# STM32G070_prototype.net
KiCad netlist of a schematic drawn in Altium Designer
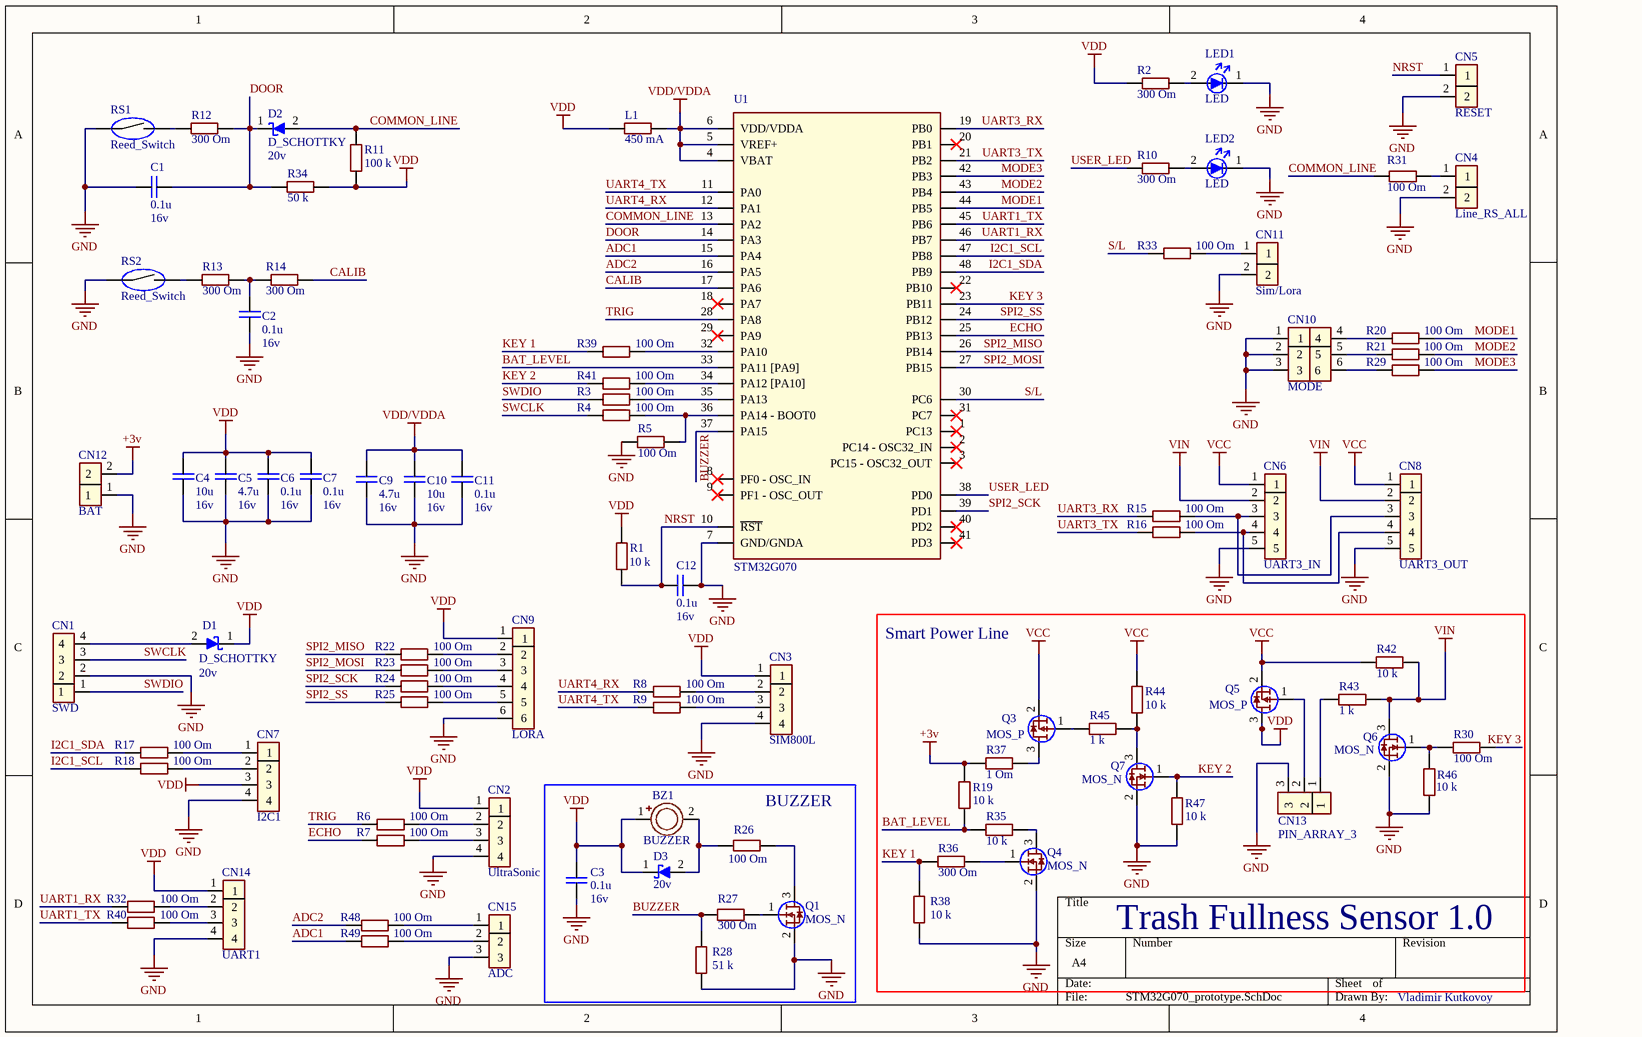
[diagram p0: STM32G070_prototype.SchDoc]

(export (version "E")
  (design (tool "Eeschema 10.0.6"))
  (components
    (comp (ref "BZ1") (value "BUZZER") (footprint "VK_Lib:BUZZER") (libsource (lib "Sound") (part "BUZZER")))
    (comp (ref "C1")
      (value "Capacitor")
      (footprint "VK_Lib:CAPC06003")
      (fields (field (name "СAPACITY") "0.1u") (field (name "VOLTAGE") "16v"))
      (libsource (lib "VK_Lib") (part "Capacitor"))
    )
    (comp (ref "C2")
      (value "Capacitor")
      (footprint "VK_Lib:CAP_0603")
      (fields (field (name "СAPACITY") "0.1u") (field (name "VOLTAGE") "16v"))
      (libsource (lib "PassiveComponents") (part "Capacitor"))
    )
    (comp (ref "C3")
      (value "Capacitor")
      (footprint "VK_Lib:CAP_0603")
      (fields (field (name "СAPACITY") "0.1u") (field (name "VOLTAGE") "16v"))
      (libsource (lib "PassiveComponents") (part "Capacitor"))
    )
    (comp (ref "C4")
      (value "~")
      (footprint "CAPC06003")
      (fields (field (name "СAPACITY") "10u") (field (name "VOLTAGE") "16v"))
      (libsource (lib "PassiveComponents") (part "Capacitor"))
    )
    (comp (ref "C5")
      (value "Capacitor")
      (footprint "VK_Lib:CAPC06003")
      (fields (field (name "СAPACITY") "4.7u") (field (name "VOLTAGE") "16v"))
      (libsource (lib "VK_Lib") (part "Capacitor"))
    )
    (comp (ref "C6")
      (value "Capacitor")
      (footprint "VK_Lib:CAPC06003")
      (fields (field (name "СAPACITY") "0.1u") (field (name "VOLTAGE") "16v"))
      (libsource (lib "VK_Lib") (part "Capacitor"))
    )
    (comp (ref "C7")
      (value "Capacitor")
      (footprint "VK_Lib:CAPC06003")
      (fields (field (name "СAPACITY") "0.1u") (field (name "VOLTAGE") "16v"))
      (libsource (lib "VK_Lib") (part "Capacitor"))
    )
    (comp (ref "C9")
      (value "Capacitor")
      (footprint "VK_Lib:Cap_0603")
      (fields (field (name "СAPACITY") "4.7u") (field (name "VOLTAGE") "16v"))
      (libsource (lib "VK_Lib") (part "Capacitor"))
    )
    (comp (ref "C10")
      (value "Capacitor")
      (footprint "VK_Lib:CAP_0603")
      (fields (field (name "СAPACITY") "10u") (field (name "VOLTAGE") "16v"))
      (libsource (lib "PassiveComponents") (part "Capacitor"))
    )
    (comp (ref "C11")
      (value "Capacitor")
      (footprint "VK_Lib:Cap_0603")
      (fields (field (name "СAPACITY") "0.1u") (field (name "VOLTAGE") "16v"))
      (libsource (lib "VK_Lib") (part "Capacitor"))
    )
    (comp (ref "C12")
      (value "Capacitor")
      (footprint "VK_Lib:CAPC06003")
      (fields (field (name "СAPACITY") "0.1u") (field (name "VOLTAGE") "16v"))
      (libsource (lib "VK_Lib") (part "Capacitor"))
    )
    (comp (ref "CN1")
      (value "SWD")
      (footprint "VK_Lib:PIN_2.54_4_array")
      (libsource (lib "") (part "PIN_ARRAY_4_1"))
    )
    (comp (ref "CN2")
      (value "UltraSonic")
      (footprint "VK_Lib:PIN_2.54_4_array")
      (libsource (lib "Connector") (part "PIN_ARRAY_4"))
    )
    (comp (ref "CN3")
      (value "SIM800L")
      (footprint "VK_Lib:PIN_2.54_4_array")
      (libsource (lib "Connector") (part "PIN_ARRAY_4"))
    )
    (comp (ref "CN4")
      (value "Line_RS_ALL")
      (footprint "VK_Lib:PIN_2.54_2_ARRAY")
      (libsource (lib "") (part "PIN_ARRAY_2_1"))
    )
    (comp (ref "CN5")
      (value "RESET")
      (footprint "VK_Lib:PIN_2.54_2_ARRAY")
      (libsource (lib "") (part "PIN_ARRAY_2_1"))
    )
    (comp (ref "CN6")
      (value "UART3_IN")
      (footprint "VK_Lib:Pin_2.54_5_Array")
      (libsource (lib "Connector") (part "PIN_ARRAY_5"))
    )
    (comp (ref "CN7")
      (value "I2C1")
      (footprint "VK_Lib:PIN_2.54_4_array")
      (libsource (lib "Connector") (part "PIN_ARRAY_4"))
    )
    (comp (ref "CN8")
      (value "UART3_OUT")
      (footprint "VK_Lib:Pin_2.54_5_Array")
      (libsource (lib "Connector") (part "PIN_ARRAY_5"))
    )
    (comp (ref "CN9")
      (value "LORA")
      (footprint "VK_Lib:Pin_2.54_6_Array")
      (libsource (lib "Connector") (part "PIN_ARRAY_6"))
    )
    (comp (ref "CN10")
      (value "MODE")
      (footprint "VK_Lib:Pin_2.54_3x2_Array")
      (libsource (lib "Connector") (part "PIN_ARRAY_3x2"))
    )
    (comp (ref "CN11")
      (value "Sim/Lora")
      (footprint "VK_Lib:PIN_2.54_2_ARRAY")
      (libsource (lib "") (part "PIN_ARRAY_2_1"))
    )
    (comp (ref "CN12")
      (value "BAT")
      (footprint "VK_Lib:PIN_2.54_2_ARRAY")
      (libsource (lib "Connector") (part "PIN_ARRAY_2"))
    )
    (comp (ref "CN13")
      (value "PIN_ARRAY_3")
      (footprint "VK_Lib:Pin_2.54_3_Array")
      (libsource (lib "") (part "PIN_ARRAY_3_1"))
    )
    (comp (ref "CN14")
      (value "UART1")
      (footprint "VK_Lib:PIN_2.54_4_array")
      (libsource (lib "Connector") (part "PIN_ARRAY_4"))
    )
    (comp (ref "CN15")
      (value "ADC")
      (footprint "VK_Lib:Pin_2.54_3_Array")
      (libsource (lib "Connector") (part "PIN_ARRAY_3"))
    )
    (comp (ref "D1")
      (value "D_SCHOTTKY")
      (footprint "Diod_Shottky")
      (fields (field (name "VOLTAGE") "20v"))
      (libsource (lib "PassiveComponents") (part "Diod_Shottky"))
    )
    (comp (ref "D2")
      (value "D_SCHOTTKY")
      (footprint "Diod_Shottky")
      (fields (field (name "VOLTAGE") "20v"))
      (libsource (lib "PassiveComponents") (part "Diod_Shottky"))
    )
    (comp (ref "D3")
      (value "D_SCHOTTKY")
      (footprint "Diod_Shottky")
      (fields (field (name "VOLTAGE") "20v"))
      (libsource (lib "PassiveComponents") (part "Diod_Shottky"))
    )
    (comp (ref "L1")
      (value "450 mA")
      (footprint "VK_Lib:RES_0603")
      (description "BLM18BB221SN1D")
      (libsource (lib "VK_Lib") (part "Filter"))
    )
    (comp (ref "LED1") (value "LED") (footprint "VK_Lib:Led_0603_Red") (libsource (lib "") (part "LED_1")))
    (comp (ref "LED2")
      (value "LED")
      (footprint "VK_Lib:Led_0603_Red")
      (libsource (lib "PassiveComponents") (part "LED"))
    )
    (comp (ref "Q1") (value "MOS_N") (footprint "SOT23-3") (libsource (lib "Semicon") (part "MOS_N")))
    (comp (ref "Q3") (value "MOS_P") (footprint "SOT23-3") (libsource (lib "Semicon") (part "MOS_P")))
    (comp (ref "Q4") (value "MOS_N") (footprint "SOT23-3") (libsource (lib "Semicon") (part "MOS_N")))
    (comp (ref "Q5") (value "MOS_P") (footprint "SOT23-3") (libsource (lib "Semicon") (part "MOS_P")))
    (comp (ref "Q6") (value "MOS_N") (footprint "SOT23-3") (libsource (lib "Semicon") (part "MOS_N")))
    (comp (ref "Q7") (value "MOS_N") (footprint "SOT23-3") (libsource (lib "Semicon") (part "MOS_N")))
    (comp (ref "R1") (value "10 k") (footprint "VK_Lib:RES_0603") (libsource (lib "") (part "Resistor_2")))
    (comp (ref "R2")
      (value "300 Om")
      (footprint "VK_Lib:RES_0603")
      (libsource (lib "VK_Lib") (part "Resistor"))
    )
    (comp (ref "R3")
      (value "100 Om")
      (footprint "VK_Lib:RES_0603")
      (libsource (lib "VK_Lib") (part "Resistor"))
    )
    (comp (ref "R4")
      (value "100 Om")
      (footprint "VK_Lib:RES_0603")
      (libsource (lib "VK_Lib") (part "Resistor"))
    )
    (comp (ref "R5")
      (value "100 Om")
      (footprint "VK_Lib:RES_0603")
      (libsource (lib "VK_Lib") (part "Resistor"))
    )
    (comp (ref "R6")
      (value "100 Om")
      (footprint "VK_Lib:RES_0603")
      (libsource (lib "VK_Lib") (part "Resistor"))
    )
    (comp (ref "R7")
      (value "100 Om")
      (footprint "VK_Lib:RES_0603")
      (libsource (lib "VK_Lib") (part "Resistor"))
    )
    (comp (ref "R8")
      (value "100 Om")
      (footprint "VK_Lib:RES_0603")
      (libsource (lib "VK_Lib") (part "Resistor"))
    )
    (comp (ref "R9")
      (value "100 Om")
      (footprint "VK_Lib:RES_0603")
      (libsource (lib "VK_Lib") (part "Resistor"))
    )
    (comp (ref "R10")
      (value "300 Om")
      (footprint "VK_Lib:RES_0603")
      (libsource (lib "VK_Lib") (part "Resistor"))
    )
    (comp (ref "R11") (value "100 k") (footprint "VK_Lib:RES_0603") (libsource (lib "") (part "Resistor_2")))
    (comp (ref "R12") (value "300 Om") (footprint "VK_Lib:RES_0603") (libsource (lib "") (part "Resistor_1")))
    (comp (ref "R13") (value "300 Om") (footprint "VK_Lib:RES_0603") (libsource (lib "") (part "Resistor_1")))
    (comp (ref "R14")
      (value "300 Om")
      (footprint "VK_Lib:RES_0603")
      (libsource (lib "VK_Lib") (part "Resistor"))
    )
    (comp (ref "R15")
      (value "100 Om")
      (footprint "VK_Lib:RES_0603")
      (libsource (lib "VK_Lib") (part "Resistor"))
    )
    (comp (ref "R16")
      (value "100 Om")
      (footprint "VK_Lib:RES_0603")
      (libsource (lib "VK_Lib") (part "Resistor"))
    )
    (comp (ref "R17")
      (value "100 Om")
      (footprint "VK_Lib:RES_0603")
      (libsource (lib "VK_Lib") (part "Resistor"))
    )
    (comp (ref "R18")
      (value "100 Om")
      (footprint "VK_Lib:RES_0603")
      (libsource (lib "VK_Lib") (part "Resistor"))
    )
    (comp (ref "R19") (value "10 k") (footprint "VK_Lib:RES_0603") (libsource (lib "") (part "Resistor_3")))
    (comp (ref "R20")
      (value "100 Om")
      (footprint "VK_Lib:RES_0603")
      (libsource (lib "VK_Lib") (part "Resistor"))
    )
    (comp (ref "R21")
      (value "100 Om")
      (footprint "VK_Lib:RES_0603")
      (libsource (lib "VK_Lib") (part "Resistor"))
    )
    (comp (ref "R22")
      (value "100 Om")
      (footprint "VK_Lib:RES_0603")
      (libsource (lib "VK_Lib") (part "Resistor"))
    )
    (comp (ref "R23")
      (value "100 Om")
      (footprint "VK_Lib:RES_0603")
      (libsource (lib "VK_Lib") (part "Resistor"))
    )
    (comp (ref "R24")
      (value "100 Om")
      (footprint "VK_Lib:RES_0603")
      (libsource (lib "VK_Lib") (part "Resistor"))
    )
    (comp (ref "R25")
      (value "100 Om")
      (footprint "VK_Lib:RES_0603")
      (libsource (lib "VK_Lib") (part "Resistor"))
    )
    (comp (ref "R26")
      (value "100 Om")
      (footprint "VK_Lib:RES_0603")
      (libsource (lib "PassiveComponents") (part "Resistor"))
    )
    (comp (ref "R27")
      (value "300 Om")
      (footprint "VK_Lib:RES_0603")
      (libsource (lib "PassiveComponents") (part "Resistor"))
    )
    (comp (ref "R28") (value "51 k") (footprint "VK_Lib:RES_0603") (libsource (lib "") (part "Resistor_3")))
    (comp (ref "R29")
      (value "100 Om")
      (footprint "VK_Lib:RES_0603")
      (libsource (lib "VK_Lib") (part "Resistor"))
    )
    (comp (ref "R30") (value "100 Om") (footprint "VK_Lib:RES_0603") (libsource (lib "") (part "Resistor_1")))
    (comp (ref "R31")
      (value "100 Om")
      (footprint "VK_Lib:RES_0603")
      (libsource (lib "VK_Lib") (part "Resistor"))
    )
    (comp (ref "R32")
      (value "100 Om")
      (footprint "VK_Lib:RES_0603")
      (libsource (lib "VK_Lib") (part "Resistor"))
    )
    (comp (ref "R33")
      (value "100 Om")
      (footprint "VK_Lib:RES_0603")
      (libsource (lib "VK_Lib") (part "Resistor"))
    )
    (comp (ref "R34")
      (value "50 k")
      (footprint "VK_Lib:RES_0603")
      (libsource (lib "VK_Lib") (part "Resistor"))
    )
    (comp (ref "R35") (value "10 k") (footprint "VK_Lib:RES_0603") (libsource (lib "") (part "Resistor_1")))
    (comp (ref "R36")
      (value "300 Om")
      (footprint "VK_Lib:RES_0603")
      (libsource (lib "PassiveComponents") (part "Resistor"))
    )
    (comp (ref "R37")
      (value "1 Om")
      (footprint "VK_Lib:Res_0805")
      (libsource (lib "PassiveComponents") (part "Resistor"))
    )
    (comp (ref "R38") (value "10 k") (footprint "VK_Lib:RES_0603") (libsource (lib "") (part "Resistor_3")))
    (comp (ref "R39")
      (value "100 Om")
      (footprint "VK_Lib:RES_0603")
      (libsource (lib "VK_Lib") (part "Resistor"))
    )
    (comp (ref "R40")
      (value "100 Om")
      (footprint "VK_Lib:RES_0603")
      (libsource (lib "VK_Lib") (part "Resistor"))
    )
    (comp (ref "R41")
      (value "100 Om")
      (footprint "VK_Lib:RES_0603")
      (libsource (lib "VK_Lib") (part "Resistor"))
    )
    (comp (ref "R42")
      (value "10 k")
      (footprint "VK_Lib:RES_0603")
      (libsource (lib "PassiveComponents") (part "Resistor"))
    )
    (comp (ref "R43")
      (value "1 k")
      (footprint "VK_Lib:RES_0603")
      (libsource (lib "PassiveComponents") (part "Resistor"))
    )
    (comp (ref "R44") (value "10 k") (footprint "VK_Lib:RES_0603") (libsource (lib "") (part "Resistor_2")))
    (comp (ref "R45")
      (value "1 k")
      (footprint "VK_Lib:RES_0603")
      (libsource (lib "PassiveComponents") (part "Resistor"))
    )
    (comp (ref "R46") (value "10 k") (footprint "VK_Lib:RES_0603") (libsource (lib "") (part "Resistor_3")))
    (comp (ref "R47") (value "10 k") (footprint "VK_Lib:RES_0603") (libsource (lib "") (part "Resistor_2")))
    (comp (ref "R48")
      (value "100 Om")
      (footprint "VK_Lib:RES_0603")
      (libsource (lib "VK_Lib") (part "Resistor"))
    )
    (comp (ref "R49")
      (value "100 Om")
      (footprint "VK_Lib:RES_0603")
      (libsource (lib "VK_Lib") (part "Resistor"))
    )
    (comp (ref "RS1")
      (value "Reed_Switch")
      (footprint "VK_Lib:PIN_2.54_2_ARRAY")
      (libsource (lib "Switch") (part "Reed_Switch"))
    )
    (comp (ref "RS2")
      (value "Reed_Switch")
      (footprint "VK_Lib:PIN_2.54_2_ARRAY")
      (libsource (lib "Switch") (part "Reed_Switch"))
    )
    (comp (ref "U1")
      (value "STM32G070")
      (footprint "VK_Lib:LQFP48")
      (libsource (lib "Processors") (part "STM32G070"))
    )
  )
  (nets
    (net (code "1") (name "+3v") (class "Default")
      (node (ref "CN12") (pin "2") (pinfunction "2_2") (pintype "passive"))
      (node (ref "R19") (pin "2") (pinfunction "2_2") (pintype "passive"))
      (node (ref "R37") (pin "1") (pinfunction "1_1") (pintype "passive"))
    )
    (net (code "2") (name "/ADC1") (class "Default")
      (node (ref "R49") (pin "1") (pinfunction "1_1") (pintype "passive"))
      (node (ref "U1") (pin "15") (pinfunction "PA4_15") (pintype "passive"))
    )
    (net (code "3") (name "/ADC2") (class "Default")
      (node (ref "R48") (pin "1") (pinfunction "1_1") (pintype "passive"))
      (node (ref "U1") (pin "16") (pinfunction "PA5_16") (pintype "passive"))
    )
    (net (code "4") (name "/BAT_LEVEL") (class "Default")
      (node (ref "R19") (pin "1") (pinfunction "1_1") (pintype "passive"))
      (node (ref "R35") (pin "2") (pinfunction "2_2") (pintype "passive"))
      (node (ref "U1") (pin "33") (pinfunction "PA11_[PA9]_33") (pintype "passive"))
    )
    (net (code "5") (name "/BUZZER") (class "Default")
      (node (ref "R27") (pin "1") (pinfunction "1_1") (pintype "passive"))
      (node (ref "R28") (pin "2") (pinfunction "2_2") (pintype "passive"))
      (node (ref "U1") (pin "37") (pinfunction "PA15_37") (pintype "passive"))
    )
    (net (code "6") (name "/CALIB") (class "Default")
      (node (ref "R14") (pin "2") (pinfunction "2_2") (pintype "passive"))
      (node (ref "U1") (pin "17") (pinfunction "PA6_17") (pintype "passive"))
    )
    (net (code "7") (name "/COMMON_LINE") (class "Default")
      (node (ref "D2") (pin "2") (pinfunction "2_2") (pintype "passive"))
      (node (ref "R11") (pin "2") (pinfunction "2_2") (pintype "passive"))
      (node (ref "R31") (pin "1") (pinfunction "1_1") (pintype "passive"))
      (node (ref "U1") (pin "13") (pinfunction "PA2_13") (pintype "passive"))
    )
    (net (code "8") (name "/DOOR") (class "Default")
      (node (ref "C1") (pin "1") (pinfunction "1_1") (pintype "passive"))
      (node (ref "D2") (pin "1") (pinfunction "1_1") (pintype "passive"))
      (node (ref "R12") (pin "1") (pinfunction "1_1") (pintype "passive"))
      (node (ref "R34") (pin "1") (pinfunction "1_1") (pintype "passive"))
      (node (ref "U1") (pin "14") (pinfunction "PA3_14") (pintype "passive"))
    )
    (net (code "9") (name "/ECHO") (class "Default")
      (node (ref "R7") (pin "1") (pinfunction "1_1") (pintype "passive"))
      (node (ref "U1") (pin "25") (pinfunction "PB13_25") (pintype "passive"))
    )
    (net (code "10") (name "/I2C1_SCL") (class "Default")
      (node (ref "R18") (pin "1") (pinfunction "1_1") (pintype "passive"))
      (node (ref "U1") (pin "47") (pinfunction "PB8_47") (pintype "passive"))
    )
    (net (code "11") (name "/I2C1_SDA") (class "Default")
      (node (ref "R17") (pin "1") (pinfunction "1_1") (pintype "passive"))
      (node (ref "U1") (pin "48") (pinfunction "PB9_48") (pintype "passive"))
    )
    (net (code "12") (name "/KEY 1") (class "Default")
      (node (ref "R36") (pin "1") (pinfunction "1_1") (pintype "passive"))
      (node (ref "R38") (pin "2") (pinfunction "2_2") (pintype "passive"))
      (node (ref "R39") (pin "1") (pinfunction "1_1") (pintype "passive"))
    )
    (net (code "13") (name "/KEY 2") (class "Default")
      (node (ref "Q7") (pin "1") (pinfunction "G_1") (pintype "passive"))
      (node (ref "R41") (pin "1") (pinfunction "1_1") (pintype "passive"))
      (node (ref "R47") (pin "1") (pinfunction "1_1") (pintype "passive"))
    )
    (net (code "14") (name "/KEY 3") (class "Default")
      (node (ref "R30") (pin "1") (pinfunction "1_1") (pintype "passive"))
      (node (ref "U1") (pin "23") (pinfunction "PB11_23") (pintype "passive"))
    )
    (net (code "15") (name "/MODE1") (class "Default")
      (node (ref "R20") (pin "2") (pinfunction "2_2") (pintype "passive"))
      (node (ref "U1") (pin "44") (pinfunction "PB5_44") (pintype "passive"))
    )
    (net (code "16") (name "/MODE2") (class "Default")
      (node (ref "R21") (pin "2") (pinfunction "2_2") (pintype "passive"))
      (node (ref "U1") (pin "43") (pinfunction "PB4_43") (pintype "passive"))
    )
    (net (code "17") (name "/MODE3") (class "Default")
      (node (ref "R29") (pin "2") (pinfunction "2_2") (pintype "passive"))
      (node (ref "U1") (pin "42") (pinfunction "PB3_42") (pintype "passive"))
    )
    (net (code "18") (name "/NRST") (class "Default")
      (node (ref "C12") (pin "2") (pinfunction "2_2") (pintype "passive"))
      (node (ref "CN5") (pin "1") (pinfunction "1_1") (pintype "passive"))
      (node (ref "R1") (pin "1") (pinfunction "1_1") (pintype "passive"))
      (node (ref "U1") (pin "10") (pinfunction "~{RST}_10") (pintype "passive"))
    )
    (net (code "19") (name "/SPI2_MISO") (class "Default")
      (node (ref "R22") (pin "1") (pinfunction "1_1") (pintype "passive"))
      (node (ref "U1") (pin "26") (pinfunction "PB14_26") (pintype "passive"))
    )
    (net (code "20") (name "/SPI2_MOSI") (class "Default")
      (node (ref "R23") (pin "1") (pinfunction "1_1") (pintype "passive"))
      (node (ref "U1") (pin "27") (pinfunction "PB15_27") (pintype "passive"))
    )
    (net (code "21") (name "/SPI2_SCK") (class "Default")
      (node (ref "R24") (pin "1") (pinfunction "1_1") (pintype "passive"))
      (node (ref "U1") (pin "39") (pinfunction "PD1_39") (pintype "passive"))
    )
    (net (code "22") (name "/SPI2_SS") (class "Default")
      (node (ref "R25") (pin "1") (pinfunction "1_1") (pintype "passive"))
      (node (ref "U1") (pin "24") (pinfunction "PB12_24") (pintype "passive"))
    )
    (net (code "23") (name "/SWCLK") (class "Default")
      (node (ref "CN1") (pin "3") (pinfunction "3_3") (pintype "passive"))
      (node (ref "R4") (pin "1") (pinfunction "1_1") (pintype "passive"))
    )
    (net (code "24") (name "/SWDIO") (class "Default")
      (node (ref "CN1") (pin "1") (pinfunction "1_1") (pintype "passive"))
      (node (ref "R3") (pin "1") (pinfunction "1_1") (pintype "passive"))
    )
    (net (code "25") (name "/S{slash}L") (class "Default")
      (node (ref "R33") (pin "1") (pinfunction "1_1") (pintype "passive"))
      (node (ref "U1") (pin "30") (pinfunction "PС6_30") (pintype "passive"))
    )
    (net (code "26") (name "/TRIG") (class "Default")
      (node (ref "R6") (pin "1") (pinfunction "1_1") (pintype "passive"))
      (node (ref "U1") (pin "28") (pinfunction "PA8_28") (pintype "passive"))
    )
    (net (code "27") (name "/UART1_RX") (class "Default")
      (node (ref "R32") (pin "1") (pinfunction "1_1") (pintype "passive"))
      (node (ref "U1") (pin "46") (pinfunction "PB7_46") (pintype "passive"))
    )
    (net (code "28") (name "/UART1_TX") (class "Default")
      (node (ref "R40") (pin "1") (pinfunction "1_1") (pintype "passive"))
      (node (ref "U1") (pin "45") (pinfunction "PB6_45") (pintype "passive"))
    )
    (net (code "29") (name "/UART3_RX") (class "Default")
      (node (ref "R15") (pin "1") (pinfunction "1_1") (pintype "passive"))
      (node (ref "U1") (pin "19") (pinfunction "PB0_19") (pintype "passive"))
    )
    (net (code "30") (name "/UART3_TX") (class "Default")
      (node (ref "R16") (pin "1") (pinfunction "1_1") (pintype "passive"))
      (node (ref "U1") (pin "21") (pinfunction "PB2_21") (pintype "passive"))
    )
    (net (code "31") (name "/UART4_RX") (class "Default")
      (node (ref "R8") (pin "1") (pinfunction "1_1") (pintype "passive"))
      (node (ref "U1") (pin "12") (pinfunction "PA1_12") (pintype "passive"))
    )
    (net (code "32") (name "/UART4_TX") (class "Default")
      (node (ref "R9") (pin "1") (pinfunction "1_1") (pintype "passive"))
      (node (ref "U1") (pin "11") (pinfunction "PA0_11") (pintype "passive"))
    )
    (net (code "33") (name "/USER_LED") (class "Default")
      (node (ref "R10") (pin "1") (pinfunction "1_1") (pintype "passive"))
      (node (ref "U1") (pin "38") (pinfunction "PD0_38") (pintype "passive"))
    )
    (net (code "34") (name "GND") (class "Default")
      (node (ref "C1") (pin "2") (pinfunction "2_2") (pintype "passive"))
      (node (ref "C10") (pin "1") (pinfunction "1_1") (pintype "passive"))
      (node (ref "C11") (pin "1") (pinfunction "1_1") (pintype "passive"))
      (node (ref "C12") (pin "1") (pinfunction "1_1") (pintype "passive"))
      (node (ref "C2") (pin "1") (pinfunction "1_1") (pintype "passive"))
      (node (ref "C3") (pin "1") (pinfunction "1_1") (pintype "passive"))
      (node (ref "C4") (pin "1") (pinfunction "1_1") (pintype "passive"))
      (node (ref "C5") (pin "1") (pinfunction "1_1") (pintype "passive"))
      (node (ref "C6") (pin "1") (pinfunction "1_1") (pintype "passive"))
      (node (ref "C7") (pin "1") (pinfunction "1_1") (pintype "passive"))
      (node (ref "C9") (pin "1") (pinfunction "1_1") (pintype "passive"))
      (node (ref "CN1") (pin "2") (pinfunction "2_2") (pintype "passive"))
      (node (ref "CN10") (pin "1") (pinfunction "1_1") (pintype "passive"))
      (node (ref "CN10") (pin "2") (pinfunction "2_2") (pintype "passive"))
      (node (ref "CN10") (pin "3") (pinfunction "3_3") (pintype "passive"))
      (node (ref "CN11") (pin "2") (pinfunction "2_2") (pintype "passive"))
      (node (ref "CN12") (pin "1") (pinfunction "1_1") (pintype "passive"))
      (node (ref "CN13") (pin "3") (pinfunction "3_3") (pintype "passive"))
      (node (ref "CN14") (pin "4") (pinfunction "4_4") (pintype "passive"))
      (node (ref "CN15") (pin "3") (pinfunction "3_3") (pintype "passive"))
      (node (ref "CN2") (pin "4") (pinfunction "4_4") (pintype "passive"))
      (node (ref "CN3") (pin "4") (pinfunction "4_4") (pintype "passive"))
      (node (ref "CN4") (pin "2") (pinfunction "2_2") (pintype "passive"))
      (node (ref "CN5") (pin "2") (pinfunction "2_2") (pintype "passive"))
      (node (ref "CN6") (pin "5") (pinfunction "5_5") (pintype "passive"))
      (node (ref "CN7") (pin "4") (pinfunction "4_4") (pintype "passive"))
      (node (ref "CN8") (pin "5") (pinfunction "5_5") (pintype "passive"))
      (node (ref "CN9") (pin "6") (pinfunction "6_6") (pintype "passive"))
      (node (ref "LED1") (pin "1") (pinfunction "1_1") (pintype "passive"))
      (node (ref "LED2") (pin "1") (pinfunction "1_1") (pintype "passive"))
      (node (ref "Q1") (pin "2") (pinfunction "S_2") (pintype "passive"))
      (node (ref "Q4") (pin "2") (pinfunction "S_2") (pintype "passive"))
      (node (ref "Q6") (pin "2") (pinfunction "S_2") (pintype "passive"))
      (node (ref "Q7") (pin "2") (pinfunction "S_2") (pintype "passive"))
      (node (ref "R28") (pin "1") (pinfunction "1_1") (pintype "passive"))
      (node (ref "R38") (pin "1") (pinfunction "1_1") (pintype "passive"))
      (node (ref "R46") (pin "1") (pinfunction "1_1") (pintype "passive"))
      (node (ref "R47") (pin "2") (pinfunction "2_2") (pintype "passive"))
      (node (ref "R5") (pin "1") (pinfunction "1_1") (pintype "passive"))
      (node (ref "RS1") (pin "1") (pinfunction "1_1") (pintype "passive"))
      (node (ref "RS2") (pin "1") (pinfunction "1_1") (pintype "passive"))
      (node (ref "U1") (pin "7") (pinfunction "GND/GNDA_7") (pintype "power_in"))
    )
    (net (code "35") (name "Net-(BZ1-Pad2)") (class "Default")
      (node (ref "BZ1") (pin "2") (pinfunction "2_2") (pintype "passive"))
      (node (ref "D3") (pin "2") (pinfunction "2_2") (pintype "passive"))
      (node (ref "R26") (pin "1") (pinfunction "1_1") (pintype "passive"))
    )
    (net (code "36") (name "Net-(C2-Pad2)") (class "Default")
      (node (ref "C2") (pin "2") (pinfunction "2_2") (pintype "passive"))
      (node (ref "R13") (pin "1") (pinfunction "1_1") (pintype "passive"))
      (node (ref "R14") (pin "1") (pinfunction "1_1") (pintype "passive"))
    )
    (net (code "37") (name "Net-(CN1-Pad4)") (class "Default")
      (node (ref "CN1") (pin "4") (pinfunction "4_4") (pintype "passive"))
      (node (ref "D1") (pin "2") (pinfunction "2_2") (pintype "passive"))
    )
    (net (code "38") (name "Net-(CN2-Pad2)") (class "Default")
      (node (ref "CN2") (pin "2") (pinfunction "2_2") (pintype "passive"))
      (node (ref "R6") (pin "2") (pinfunction "2_2") (pintype "passive"))
    )
    (net (code "39") (name "Net-(CN2-Pad3)") (class "Default")
      (node (ref "CN2") (pin "3") (pinfunction "3_3") (pintype "passive"))
      (node (ref "R7") (pin "2") (pinfunction "2_2") (pintype "passive"))
    )
    (net (code "40") (name "Net-(CN3-Pad2)") (class "Default")
      (node (ref "CN3") (pin "2") (pinfunction "2_2") (pintype "passive"))
      (node (ref "R8") (pin "2") (pinfunction "2_2") (pintype "passive"))
    )
    (net (code "41") (name "Net-(CN3-Pad3)") (class "Default")
      (node (ref "CN3") (pin "3") (pinfunction "3_3") (pintype "passive"))
      (node (ref "R9") (pin "2") (pinfunction "2_2") (pintype "passive"))
    )
    (net (code "42") (name "Net-(CN4-Pad1)") (class "Default")
      (node (ref "CN4") (pin "1") (pinfunction "1_1") (pintype "passive"))
      (node (ref "R31") (pin "2") (pinfunction "2_2") (pintype "passive"))
    )
    (net (code "43") (name "Net-(CN6-Pad3)") (class "Default")
      (node (ref "CN6") (pin "3") (pinfunction "3_3") (pintype "passive"))
      (node (ref "CN8") (pin "3") (pinfunction "3_3") (pintype "passive"))
      (node (ref "R15") (pin "2") (pinfunction "2_2") (pintype "passive"))
    )
    (net (code "44") (name "Net-(CN6-Pad4)") (class "Default")
      (node (ref "CN6") (pin "4") (pinfunction "4_4") (pintype "passive"))
      (node (ref "CN8") (pin "4") (pinfunction "4_4") (pintype "passive"))
      (node (ref "R16") (pin "2") (pinfunction "2_2") (pintype "passive"))
    )
    (net (code "45") (name "Net-(CN7-Pad1)") (class "Default")
      (node (ref "CN7") (pin "1") (pinfunction "1_1") (pintype "passive"))
      (node (ref "R17") (pin "2") (pinfunction "2_2") (pintype "passive"))
    )
    (net (code "46") (name "Net-(CN7-Pad2)") (class "Default")
      (node (ref "CN7") (pin "2") (pinfunction "2_2") (pintype "passive"))
      (node (ref "R18") (pin "2") (pinfunction "2_2") (pintype "passive"))
    )
    (net (code "47") (name "Net-(CN9-Pad2)") (class "Default")
      (node (ref "CN9") (pin "2") (pinfunction "2_2") (pintype "passive"))
      (node (ref "R22") (pin "2") (pinfunction "2_2") (pintype "passive"))
    )
    (net (code "48") (name "Net-(CN9-Pad3)") (class "Default")
      (node (ref "CN9") (pin "3") (pinfunction "3_3") (pintype "passive"))
      (node (ref "R23") (pin "2") (pinfunction "2_2") (pintype "passive"))
    )
    (net (code "49") (name "Net-(CN9-Pad4)") (class "Default")
      (node (ref "CN9") (pin "4") (pinfunction "4_4") (pintype "passive"))
      (node (ref "R24") (pin "2") (pinfunction "2_2") (pintype "passive"))
    )
    (net (code "50") (name "Net-(CN9-Pad5)") (class "Default")
      (node (ref "CN9") (pin "5") (pinfunction "5_5") (pintype "passive"))
      (node (ref "R25") (pin "2") (pinfunction "2_2") (pintype "passive"))
    )
    (net (code "51") (name "Net-(CN10-Pad4)") (class "Default")
      (node (ref "CN10") (pin "4") (pinfunction "4_4") (pintype "passive"))
      (node (ref "R20") (pin "1") (pinfunction "1_1") (pintype "passive"))
    )
    (net (code "52") (name "Net-(CN10-Pad5)") (class "Default")
      (node (ref "CN10") (pin "5") (pinfunction "5_5") (pintype "passive"))
      (node (ref "R21") (pin "1") (pinfunction "1_1") (pintype "passive"))
    )
    (net (code "53") (name "Net-(CN10-Pad6)") (class "Default")
      (node (ref "CN10") (pin "6") (pinfunction "6_6") (pintype "passive"))
      (node (ref "R29") (pin "1") (pinfunction "1_1") (pintype "passive"))
    )
    (net (code "54") (name "Net-(CN11-Pad1)") (class "Default")
      (node (ref "CN11") (pin "1") (pinfunction "1_1") (pintype "passive"))
      (node (ref "R33") (pin "2") (pinfunction "2_2") (pintype "passive"))
    )
    (net (code "55") (name "Net-(CN13-Pad1)") (class "Default")
      (node (ref "CN13") (pin "1") (pinfunction "1_1") (pintype "passive"))
      (node (ref "R43") (pin "1") (pinfunction "1_1") (pintype "passive"))
    )
    (net (code "56") (name "Net-(CN14-Pad2)") (class "Default")
      (node (ref "CN14") (pin "2") (pinfunction "2_2") (pintype "passive"))
      (node (ref "R32") (pin "2") (pinfunction "2_2") (pintype "passive"))
    )
    (net (code "57") (name "Net-(CN14-Pad3)") (class "Default")
      (node (ref "CN14") (pin "3") (pinfunction "3_3") (pintype "passive"))
      (node (ref "R40") (pin "2") (pinfunction "2_2") (pintype "passive"))
    )
    (net (code "58") (name "Net-(CN15-Pad1)") (class "Default")
      (node (ref "CN15") (pin "1") (pinfunction "1_1") (pintype "passive"))
      (node (ref "R48") (pin "2") (pinfunction "2_2") (pintype "passive"))
    )
    (net (code "59") (name "Net-(CN15-Pad2)") (class "Default")
      (node (ref "CN15") (pin "2") (pinfunction "2_2") (pintype "passive"))
      (node (ref "R49") (pin "2") (pinfunction "2_2") (pintype "passive"))
    )
    (net (code "60") (name "Net-(LED1-Pad2)") (class "Default")
      (node (ref "LED1") (pin "2") (pinfunction "2_2") (pintype "passive"))
      (node (ref "R2") (pin "2") (pinfunction "2_2") (pintype "passive"))
    )
    (net (code "61") (name "Net-(LED2-Pad2)") (class "Default")
      (node (ref "LED2") (pin "2") (pinfunction "2_2") (pintype "passive"))
      (node (ref "R10") (pin "2") (pinfunction "2_2") (pintype "passive"))
    )
    (net (code "62") (name "Net-(Q1-D)") (class "Default")
      (node (ref "Q1") (pin "3") (pinfunction "D_3") (pintype "passive"))
      (node (ref "R26") (pin "2") (pinfunction "2_2") (pintype "passive"))
    )
    (net (code "63") (name "Net-(Q1-G)") (class "Default")
      (node (ref "Q1") (pin "1") (pinfunction "G_1") (pintype "passive"))
      (node (ref "R27") (pin "2") (pinfunction "2_2") (pintype "passive"))
    )
    (net (code "64") (name "Net-(Q3-D)") (class "Default")
      (node (ref "Q3") (pin "3") (pinfunction "D_3") (pintype "passive"))
      (node (ref "R37") (pin "2") (pinfunction "2_2") (pintype "passive"))
    )
    (net (code "65") (name "Net-(Q3-G)") (class "Default")
      (node (ref "Q3") (pin "1") (pinfunction "G_1") (pintype "passive"))
      (node (ref "R45") (pin "1") (pinfunction "1_1") (pintype "passive"))
    )
    (net (code "66") (name "Net-(Q4-D)") (class "Default")
      (node (ref "Q4") (pin "3") (pinfunction "D_3") (pintype "passive"))
      (node (ref "R35") (pin "1") (pinfunction "1_1") (pintype "passive"))
    )
    (net (code "67") (name "Net-(Q4-G)") (class "Default")
      (node (ref "Q4") (pin "1") (pinfunction "G_1") (pintype "passive"))
      (node (ref "R36") (pin "2") (pinfunction "2_2") (pintype "passive"))
    )
    (net (code "68") (name "Net-(Q5-G)") (class "Default")
      (node (ref "CN13") (pin "2") (pinfunction "2_2") (pintype "passive"))
      (node (ref "Q5") (pin "1") (pinfunction "G_1") (pintype "passive"))
    )
    (net (code "69") (name "Net-(Q6-G)") (class "Default")
      (node (ref "Q6") (pin "1") (pinfunction "G_1") (pintype "passive"))
      (node (ref "R30") (pin "2") (pinfunction "2_2") (pintype "passive"))
      (node (ref "R46") (pin "2") (pinfunction "2_2") (pintype "passive"))
    )
    (net (code "70") (name "Net-(Q7-D)") (class "Default")
      (node (ref "Q7") (pin "3") (pinfunction "D_3") (pintype "passive"))
      (node (ref "R44") (pin "2") (pinfunction "2_2") (pintype "passive"))
      (node (ref "R45") (pin "2") (pinfunction "2_2") (pintype "passive"))
    )
    (net (code "71") (name "Net-(R12-Pad2)") (class "Default")
      (node (ref "R12") (pin "2") (pinfunction "2_2") (pintype "passive"))
      (node (ref "RS1") (pin "2") (pinfunction "2_2") (pintype "passive"))
    )
    (net (code "72") (name "Net-(R13-Pad2)") (class "Default")
      (node (ref "R13") (pin "2") (pinfunction "2_2") (pintype "passive"))
      (node (ref "RS2") (pin "2") (pinfunction "2_2") (pintype "passive"))
    )
    (net (code "73") (name "Net-(U1-PA10)") (class "Default")
      (node (ref "R39") (pin "2") (pinfunction "2_2") (pintype "passive"))
      (node (ref "U1") (pin "32") (pinfunction "PA10_32") (pintype "passive"))
    )
    (net (code "74") (name "Net-(U1-PA12_[PA10])") (class "Default")
      (node (ref "R41") (pin "2") (pinfunction "2_2") (pintype "passive"))
      (node (ref "U1") (pin "34") (pinfunction "PA12_[PA10]_34") (pintype "passive"))
    )
    (net (code "75") (name "Net-(U1-PA13)") (class "Default")
      (node (ref "R3") (pin "2") (pinfunction "2_2") (pintype "passive"))
      (node (ref "U1") (pin "35") (pinfunction "PA13_35") (pintype "passive"))
    )
    (net (code "76") (name "Net-(U1-PA14_-_BOOT0)") (class "Default")
      (node (ref "R4") (pin "2") (pinfunction "2_2") (pintype "passive"))
      (node (ref "R5") (pin "2") (pinfunction "2_2") (pintype "passive"))
      (node (ref "U1") (pin "36") (pinfunction "PA14_-_BOOT0_36") (pintype "passive"))
    )
    (net (code "77") (name "VCC") (class "Default")
      (node (ref "CN6") (pin "1") (pinfunction "1_1") (pintype "passive"))
      (node (ref "CN8") (pin "1") (pinfunction "1_1") (pintype "passive"))
      (node (ref "Q3") (pin "2") (pinfunction "S_2") (pintype "passive"))
      (node (ref "Q5") (pin "2") (pinfunction "S_2") (pintype "passive"))
      (node (ref "R42") (pin "1") (pinfunction "1_1") (pintype "passive"))
      (node (ref "R44") (pin "1") (pinfunction "1_1") (pintype "passive"))
    )
    (net (code "78") (name "VDD") (class "Default")
      (node (ref "BZ1") (pin "1") (pinfunction "1_1") (pintype "passive"))
      (node (ref "C3") (pin "2") (pinfunction "2_2") (pintype "passive"))
      (node (ref "C4") (pin "2") (pinfunction "2_2") (pintype "passive"))
      (node (ref "C5") (pin "2") (pinfunction "2_2") (pintype "passive"))
      (node (ref "C6") (pin "2") (pinfunction "2_2") (pintype "passive"))
      (node (ref "C7") (pin "2") (pinfunction "2_2") (pintype "passive"))
      (node (ref "CN14") (pin "1") (pinfunction "1_1") (pintype "passive"))
      (node (ref "CN2") (pin "1") (pinfunction "1_1") (pintype "passive"))
      (node (ref "CN3") (pin "1") (pinfunction "1_1") (pintype "passive"))
      (node (ref "CN7") (pin "3") (pinfunction "3_3") (pintype "passive"))
      (node (ref "CN9") (pin "1") (pinfunction "1_1") (pintype "passive"))
      (node (ref "D1") (pin "1") (pinfunction "1_1") (pintype "passive"))
      (node (ref "D3") (pin "1") (pinfunction "1_1") (pintype "passive"))
      (node (ref "L1") (pin "1") (pinfunction "1_1") (pintype "passive"))
      (node (ref "Q5") (pin "3") (pinfunction "D_3") (pintype "passive"))
      (node (ref "R1") (pin "2") (pinfunction "2_2") (pintype "passive"))
      (node (ref "R11") (pin "1") (pinfunction "1_1") (pintype "passive"))
      (node (ref "R2") (pin "1") (pinfunction "1_1") (pintype "passive"))
      (node (ref "R34") (pin "2") (pinfunction "2_2") (pintype "passive"))
    )
    (net (code "79") (name "VDD{slash}VDDA") (class "Default")
      (node (ref "C10") (pin "2") (pinfunction "2_2") (pintype "passive"))
      (node (ref "C11") (pin "2") (pinfunction "2_2") (pintype "passive"))
      (node (ref "C9") (pin "2") (pinfunction "2_2") (pintype "passive"))
      (node (ref "L1") (pin "2") (pinfunction "2_2") (pintype "passive"))
      (node (ref "U1") (pin "4") (pinfunction "VBAT_4") (pintype "power_in"))
      (node (ref "U1") (pin "5") (pinfunction "VREF+_5") (pintype "power_in"))
      (node (ref "U1") (pin "6") (pinfunction "VDD/VDDA_6") (pintype "power_in"))
    )
    (net (code "80") (name "VIN") (class "Default")
      (node (ref "CN6") (pin "2") (pinfunction "2_2") (pintype "passive"))
      (node (ref "CN8") (pin "2") (pinfunction "2_2") (pintype "passive"))
      (node (ref "Q6") (pin "3") (pinfunction "D_3") (pintype "passive"))
      (node (ref "R42") (pin "2") (pinfunction "2_2") (pintype "passive"))
      (node (ref "R43") (pin "2") (pinfunction "2_2") (pintype "passive"))
    )
    (net (code "81") (name "unconnected-(U1-PA7-Pad18)") (class "Default")
      (node (ref "U1") (pin "18") (pinfunction "PA7_18") (pintype "passive+no_connect"))
    )
    (net (code "82") (name "unconnected-(U1-PA9-Pad29)") (class "Default")
      (node (ref "U1") (pin "29") (pinfunction "PA9_29") (pintype "passive+no_connect"))
    )
    (net (code "83") (name "unconnected-(U1-PB1-Pad20)") (class "Default")
      (node (ref "U1") (pin "20") (pinfunction "PB1_20") (pintype "passive+no_connect"))
    )
    (net (code "84") (name "unconnected-(U1-PB10-Pad22)") (class "Default")
      (node (ref "U1") (pin "22") (pinfunction "PB10_22") (pintype "passive+no_connect"))
    )
    (net (code "85") (name "unconnected-(U1-PC14_-_OSC32_IN-Pad2)") (class "Default")
      (node (ref "U1") (pin "2") (pinfunction "PC14_-_OSC32_IN_2") (pintype "passive+no_connect"))
    )
    (net (code "86") (name "unconnected-(U1-PC15_-_OSC32_OUT-Pad3)") (class "Default")
      (node (ref "U1") (pin "3") (pinfunction "PC15_-_OSC32_OUT_3") (pintype "passive+no_connect"))
    )
    (net (code "87") (name "unconnected-(U1-PD2-Pad40)") (class "Default")
      (node (ref "U1") (pin "40") (pinfunction "PD2_40") (pintype "passive+no_connect"))
    )
    (net (code "88") (name "unconnected-(U1-PD3-Pad41)") (class "Default")
      (node (ref "U1") (pin "41") (pinfunction "PD3_41") (pintype "passive+no_connect"))
    )
    (net (code "89") (name "unconnected-(U1-PF0_-_OSC_IN-Pad8)") (class "Default")
      (node (ref "U1") (pin "8") (pinfunction "PF0_-_OSC_IN_8") (pintype "passive+no_connect"))
    )
    (net (code "90") (name "unconnected-(U1-PF1_-_OSC_OUT-Pad9)") (class "Default")
      (node (ref "U1") (pin "9") (pinfunction "PF1_-_OSC_OUT_9") (pintype "passive+no_connect"))
    )
    (net (code "91") (name "unconnected-(U1-PС7-Pad31)") (class "Default")
      (node (ref "U1") (pin "31") (pinfunction "PС7_31") (pintype "passive+no_connect"))
    )
    (net (code "92") (name "unconnected-(U1-PС13-Pad1)") (class "Default")
      (node (ref "U1") (pin "1") (pinfunction "PС13_1") (pintype "passive+no_connect"))
    )
  )
)
